# Cargador_RasPi3HAT_CamSlot_v1_1.net
KiCad netlist of a schematic drawn in EAGLE
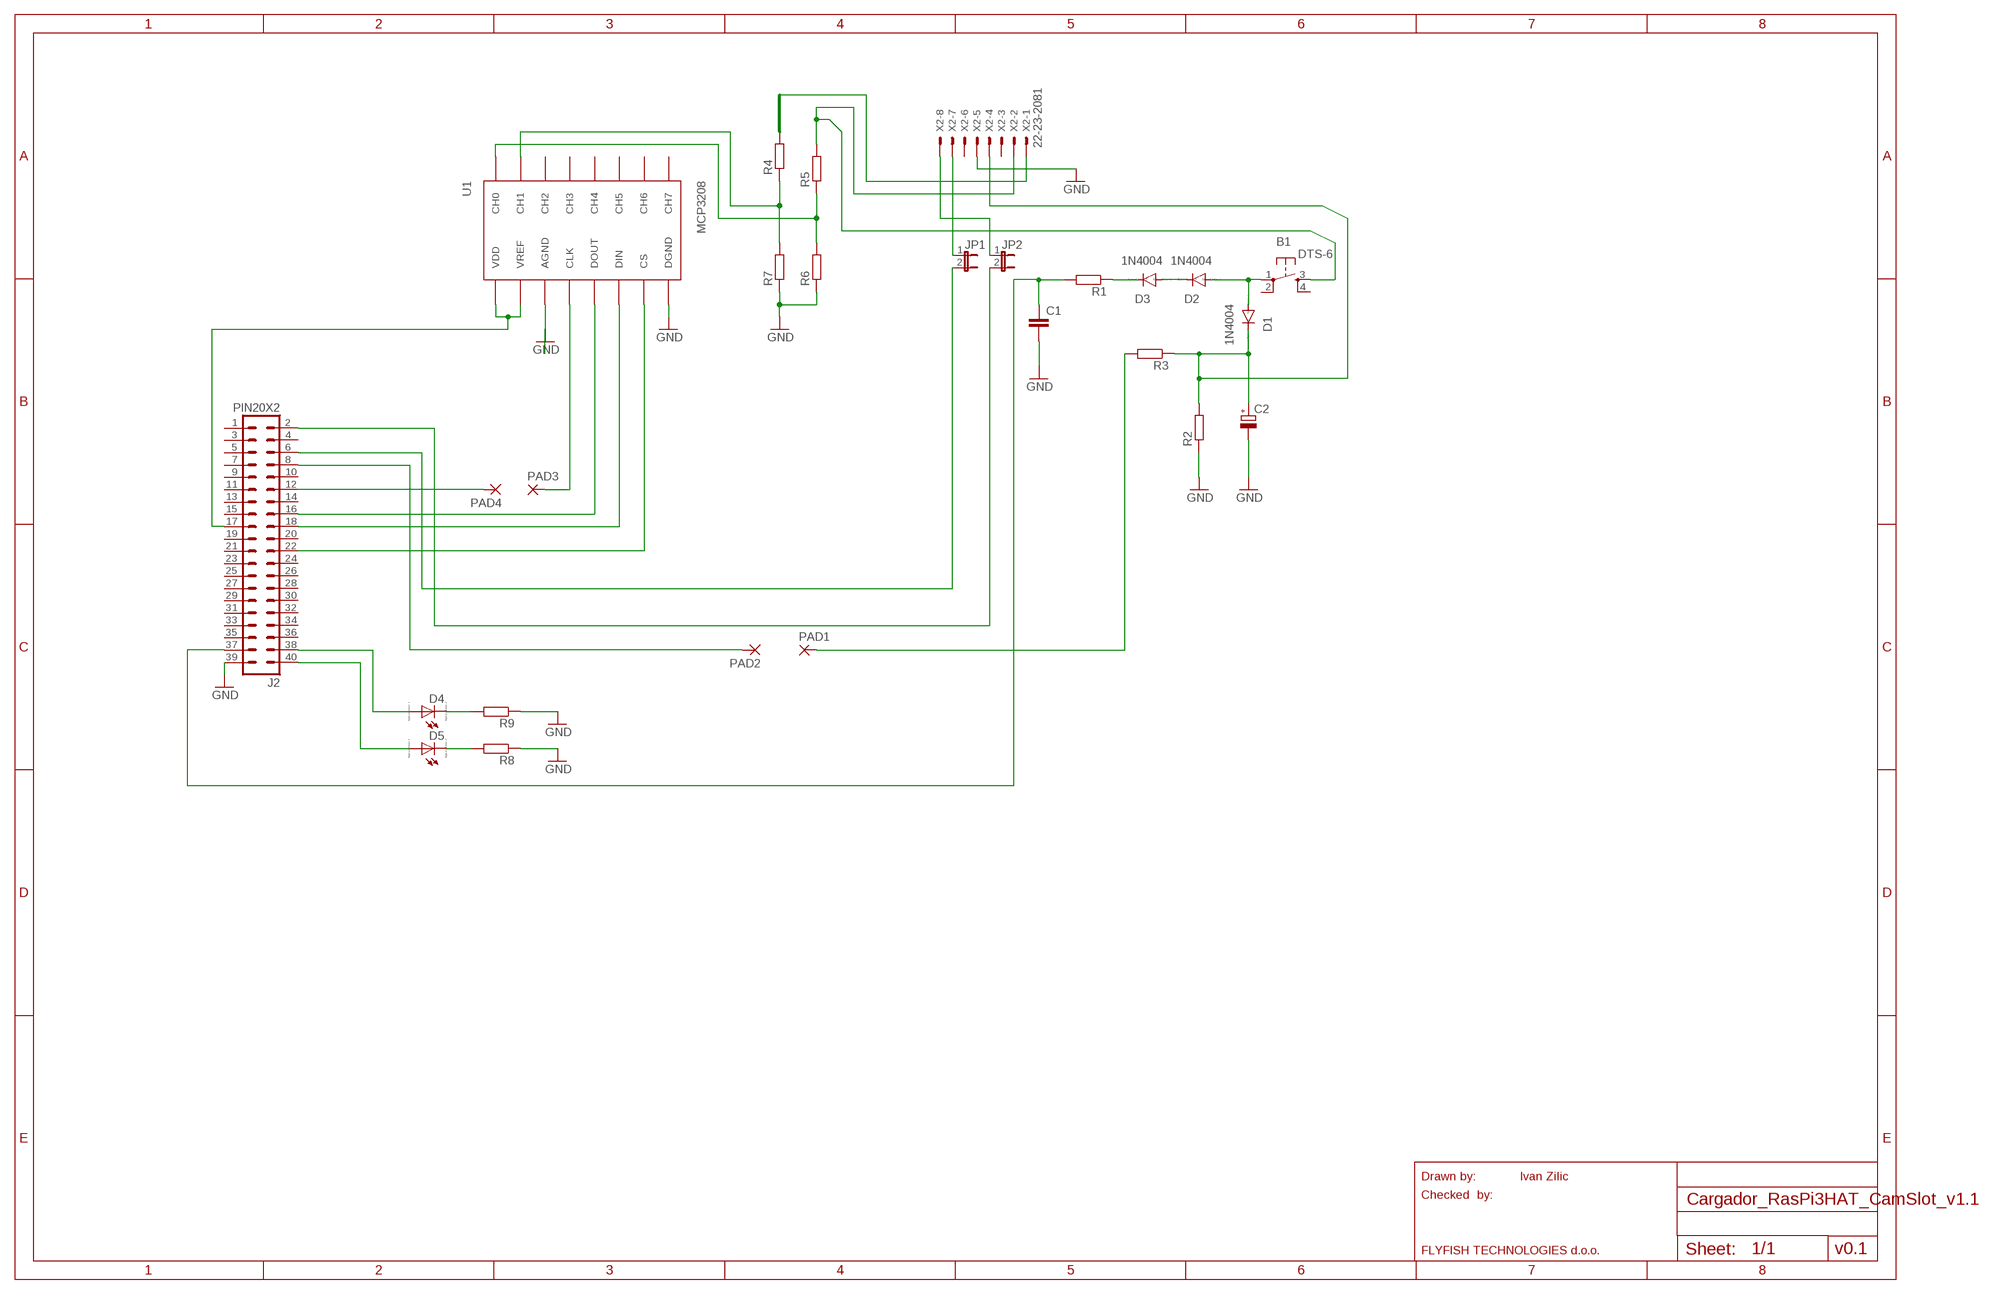
[diagram p0: schematic, sheet 1]

(export (version "E")
  (design (tool "Eeschema 10.0.6"))
  (components
    (comp (ref "B1")
      (value "DTS-6")
      (footprint "eagle-import:DTS-6")
      (libsource (lib "eagle-import") (part "DTS-6"))
    )
    (comp (ref "C1")
      (value "C2.5/2")
      (footprint "eagle-import:C2.5-2")
      (libsource (lib "eagle-import") (part "C2.5/2"))
    )
    (comp (ref "C2")
      (value "CPOL-EUE5-4")
      (footprint "eagle-import:E5-4")
      (libsource (lib "eagle-import") (part "CPOL-EUE5-4"))
    )
    (comp (ref "D1")
      (value "1N4004")
      (footprint "eagle-import:DO41-10")
      (libsource (lib "eagle-import") (part "1N4004"))
    )
    (comp (ref "D2")
      (value "1N4004")
      (footprint "eagle-import:DO41-10")
      (libsource (lib "eagle-import") (part "1N4004"))
    )
    (comp (ref "D3")
      (value "1N4004")
      (footprint "eagle-import:DO41-10")
      (libsource (lib "eagle-import") (part "1N4004"))
    )
    (comp (ref "D4")
      (value "LED_ELD260")
      (footprint "eagle-import:LED_LD260")
      (libsource (lib "eagle-import") (part "LED_ELD260"))
    )
    (comp (ref "D5")
      (value "LED_ELD260")
      (footprint "eagle-import:LED_LD260")
      (libsource (lib "eagle-import") (part "LED_ELD260"))
    )
    (comp (ref "J2")
      (value "PIN20X2")
      (footprint "eagle-import:PIN_20X2")
      (libsource (lib "eagle-import") (part "PIN20X2"))
    )
    (comp (ref "JP1")
      (value "JP1E")
      (footprint "eagle-import:JP1")
      (libsource (lib "eagle-import") (part "JP1E"))
    )
    (comp (ref "JP2")
      (value "JP1E")
      (footprint "eagle-import:JP1")
      (libsource (lib "eagle-import") (part "JP1E"))
    )
    (comp (ref "PAD1")
      (value "2,15/1,0")
      (footprint "eagle-import:2,15_1,0")
      (libsource (lib "eagle-import") (part "2,15/1,0"))
    )
    (comp (ref "PAD2")
      (value "2,15/1,0")
      (footprint "eagle-import:2,15_1,0")
      (libsource (lib "eagle-import") (part "2,15/1,0"))
    )
    (comp (ref "PAD3")
      (value "2,15/1,0")
      (footprint "eagle-import:2,15_1,0")
      (libsource (lib "eagle-import") (part "2,15/1,0"))
    )
    (comp (ref "PAD4")
      (value "2,15/1,0")
      (footprint "eagle-import:2,15_1,0")
      (libsource (lib "eagle-import") (part "2,15/1,0"))
    )
    (comp (ref "R1")
      (value "R-EU_0207/10")
      (footprint "eagle-import:0207_10")
      (libsource (lib "eagle-import") (part "R-EU_0207/10"))
    )
    (comp (ref "R2")
      (value "R-EU_0207/10")
      (footprint "eagle-import:0207_10")
      (libsource (lib "eagle-import") (part "R-EU_0207/10"))
    )
    (comp (ref "R3")
      (value "R-EU_0207/10")
      (footprint "eagle-import:0207_10")
      (libsource (lib "eagle-import") (part "R-EU_0207/10"))
    )
    (comp (ref "R4")
      (value "R-EU_0207/10")
      (footprint "eagle-import:0207_10")
      (libsource (lib "eagle-import") (part "R-EU_0207/10"))
    )
    (comp (ref "R5")
      (value "R-EU_0207/10")
      (footprint "eagle-import:0207_10")
      (libsource (lib "eagle-import") (part "R-EU_0207/10"))
    )
    (comp (ref "R6")
      (value "R-EU_0207/10")
      (footprint "eagle-import:0207_10")
      (libsource (lib "eagle-import") (part "R-EU_0207/10"))
    )
    (comp (ref "R7")
      (value "R-EU_0207/10")
      (footprint "eagle-import:0207_10")
      (libsource (lib "eagle-import") (part "R-EU_0207/10"))
    )
    (comp (ref "R8")
      (value "R-EU_0207/10")
      (footprint "eagle-import:0207_10")
      (libsource (lib "eagle-import") (part "R-EU_0207/10"))
    )
    (comp (ref "R9")
      (value "R-EU_0207/10")
      (footprint "eagle-import:0207_10")
      (libsource (lib "eagle-import") (part "R-EU_0207/10"))
    )
    (comp (ref "U1")
      (value "MCP3208")
      (footprint "eagle-import:DIL16")
      (libsource (lib "eagle-import") (part "MCP3208"))
    )
    (comp (ref "X2")
      (value "22-23-2081")
      (footprint "eagle-import:22-23-2081")
      (fields (field (name "MF") "MOLEX"))
      (libsource (lib "eagle-import") (part "22-23-2081"))
    )
  )
  (nets
    (net (code "1") (name "GND") (class "Default")
      (node (ref "C1") (pin "2") (pinfunction "2_2") (pintype "passive"))
      (node (ref "C2") (pin "-") (pinfunction "-_-") (pintype "passive"))
      (node (ref "J2") (pin "39") (pinfunction "39_39") (pintype "passive"))
      (node (ref "R2") (pin "1") (pinfunction "1_1") (pintype "passive"))
      (node (ref "R6") (pin "1") (pinfunction "1_1") (pintype "passive"))
      (node (ref "R7") (pin "1") (pinfunction "1_1") (pintype "passive"))
      (node (ref "R8") (pin "1") (pinfunction "1_1") (pintype "passive"))
      (node (ref "R9") (pin "1") (pinfunction "1_1") (pintype "passive"))
      (node (ref "U1") (pin "AGND") (pinfunction "AGND_AGND") (pintype "power_in"))
      (node (ref "U1") (pin "DGND") (pinfunction "DGND_DGND") (pintype "power_in"))
      (node (ref "X2") (pin "5") (pinfunction "S_5") (pintype "passive"))
    )
    (net (code "2") (name "Net-(B1-Pad1)") (class "Default")
      (node (ref "B1") (pin "1") (pinfunction "1_1") (pintype "passive"))
      (node (ref "D1") (pin "A") (pinfunction "A_A") (pintype "passive"))
      (node (ref "D2") (pin "A") (pinfunction "A_A") (pintype "passive"))
    )
    (net (code "3") (name "Net-(C1-Pad1)") (class "Default")
      (node (ref "C1") (pin "1") (pinfunction "1_1") (pintype "passive"))
      (node (ref "J2") (pin "37") (pinfunction "37_37") (pintype "passive"))
      (node (ref "R1") (pin "2") (pinfunction "2_2") (pintype "passive"))
    )
    (net (code "4") (name "Net-(D2-PadC)") (class "Default")
      (node (ref "D2") (pin "C") (pinfunction "C_C") (pintype "passive"))
      (node (ref "D3") (pin "A") (pinfunction "A_A") (pintype "passive"))
    )
    (net (code "5") (name "Net-(D3-PadC)") (class "Default")
      (node (ref "D3") (pin "C") (pinfunction "C_C") (pintype "passive"))
      (node (ref "R1") (pin "1") (pinfunction "1_1") (pintype "passive"))
    )
    (net (code "6") (name "Net-(D4-C)") (class "Default")
      (node (ref "D4") (pin "K") (pinfunction "C_K") (pintype "passive"))
      (node (ref "R9") (pin "2") (pinfunction "2_2") (pintype "passive"))
    )
    (net (code "7") (name "Net-(D4-PadA)") (class "Default")
      (node (ref "D4") (pin "A") (pinfunction "A_A") (pintype "passive"))
      (node (ref "J2") (pin "38") (pinfunction "38_38") (pintype "passive"))
    )
    (net (code "8") (name "Net-(D5-C)") (class "Default")
      (node (ref "D5") (pin "K") (pinfunction "C_K") (pintype "passive"))
      (node (ref "R8") (pin "2") (pinfunction "2_2") (pintype "passive"))
    )
    (net (code "9") (name "Net-(D5-PadA)") (class "Default")
      (node (ref "D5") (pin "A") (pinfunction "A_A") (pintype "passive"))
      (node (ref "J2") (pin "40") (pinfunction "40_40") (pintype "passive"))
    )
    (net (code "10") (name "Net-(J2-Pad2)") (class "Default")
      (node (ref "J2") (pin "2") (pinfunction "2_2") (pintype "passive"))
      (node (ref "JP2") (pin "2") (pinfunction "2_2") (pintype "passive"))
    )
    (net (code "11") (name "Net-(J2-Pad6)") (class "Default")
      (node (ref "J2") (pin "6") (pinfunction "6_6") (pintype "passive"))
      (node (ref "JP1") (pin "2") (pinfunction "2_2") (pintype "passive"))
    )
    (net (code "12") (name "Net-(J2-Pad16)") (class "Default")
      (node (ref "J2") (pin "16") (pinfunction "16_16") (pintype "passive"))
      (node (ref "U1") (pin "DOUT") (pinfunction "DOUT_DOUT") (pintype "output"))
    )
    (net (code "13") (name "Net-(J2-Pad17)") (class "Default")
      (node (ref "J2") (pin "17") (pinfunction "17_17") (pintype "passive"))
      (node (ref "U1") (pin "VDD") (pinfunction "VDD_VDD") (pintype "power_in"))
      (node (ref "U1") (pin "VREF") (pinfunction "VREF_VREF") (pintype "input"))
    )
    (net (code "14") (name "Net-(J2-Pad18)") (class "Default")
      (node (ref "J2") (pin "18") (pinfunction "18_18") (pintype "passive"))
      (node (ref "U1") (pin "DIN") (pinfunction "DIN_DIN") (pintype "input"))
    )
    (net (code "15") (name "Net-(J2-Pad22)") (class "Default")
      (node (ref "J2") (pin "22") (pinfunction "22_22") (pintype "passive"))
      (node (ref "U1") (pin "CS") (pinfunction "CS_CS") (pintype "input"))
    )
    (net (code "16") (name "Net-(PAD1-P)") (class "Default")
      (node (ref "PAD1") (pin "1") (pinfunction "P_1") (pintype "passive"))
      (node (ref "R3") (pin "2") (pinfunction "2_2") (pintype "passive"))
    )
    (net (code "17") (name "Net-(PAD2-P)") (class "Default")
      (node (ref "J2") (pin "8") (pinfunction "8_8") (pintype "passive"))
      (node (ref "PAD2") (pin "1") (pinfunction "P_1") (pintype "passive"))
    )
    (net (code "18") (name "Net-(PAD3-P)") (class "Default")
      (node (ref "PAD3") (pin "1") (pinfunction "P_1") (pintype "passive"))
      (node (ref "U1") (pin "CLK") (pinfunction "CLK_CLK") (pintype "input"))
    )
    (net (code "19") (name "Net-(PAD4-P)") (class "Default")
      (node (ref "J2") (pin "12") (pinfunction "12_12") (pintype "passive"))
      (node (ref "PAD4") (pin "1") (pinfunction "P_1") (pintype "passive"))
    )
    (net (code "20") (name "Net-(R4-Pad1)") (class "Default")
      (node (ref "R4") (pin "1") (pinfunction "1_1") (pintype "passive"))
      (node (ref "R7") (pin "2") (pinfunction "2_2") (pintype "passive"))
      (node (ref "U1") (pin "CH1") (pinfunction "CH1_CH1") (pintype "input"))
    )
    (net (code "21") (name "Net-(R5-Pad1)") (class "Default")
      (node (ref "R5") (pin "1") (pinfunction "1_1") (pintype "passive"))
      (node (ref "R6") (pin "2") (pinfunction "2_2") (pintype "passive"))
      (node (ref "U1") (pin "CH0") (pinfunction "CH0_CH0") (pintype "input"))
    )
    (net (code "22") (name "Net-(X2A-S)") (class "Default")
      (node (ref "R4") (pin "2") (pinfunction "2_2") (pintype "passive"))
      (node (ref "X2") (pin "1") (pinfunction "S_1") (pintype "passive"))
    )
    (net (code "23") (name "Net-(X2B-S)") (class "Default")
      (node (ref "B1") (pin "3") (pinfunction "3_3") (pintype "passive"))
      (node (ref "R5") (pin "2") (pinfunction "2_2") (pintype "passive"))
      (node (ref "X2") (pin "2") (pinfunction "S_2") (pintype "passive"))
    )
    (net (code "24") (name "Net-(X2D-S)") (class "Default")
      (node (ref "C2") (pin "+") (pinfunction "+_+") (pintype "passive"))
      (node (ref "D1") (pin "C") (pinfunction "C_C") (pintype "passive"))
      (node (ref "R2") (pin "2") (pinfunction "2_2") (pintype "passive"))
      (node (ref "R3") (pin "1") (pinfunction "1_1") (pintype "passive"))
      (node (ref "X2") (pin "4") (pinfunction "S_4") (pintype "passive"))
    )
    (net (code "25") (name "Net-(X2G-S)") (class "Default")
      (node (ref "JP1") (pin "1") (pinfunction "1_1") (pintype "passive"))
      (node (ref "X2") (pin "7") (pinfunction "S_7") (pintype "passive"))
    )
    (net (code "26") (name "Net-(X2H-S)") (class "Default")
      (node (ref "JP2") (pin "1") (pinfunction "1_1") (pintype "passive"))
      (node (ref "X2") (pin "8") (pinfunction "S_8") (pintype "passive"))
    )
    (net (code "27") (name "unconnected-(B1-Pad2)") (class "Default")
      (node (ref "B1") (pin "2") (pinfunction "2_2") (pintype "passive"))
    )
    (net (code "28") (name "unconnected-(B1-Pad4)") (class "Default")
      (node (ref "B1") (pin "4") (pinfunction "4_4") (pintype "passive"))
    )
    (net (code "29") (name "unconnected-(J2-Pad1)") (class "Default")
      (node (ref "J2") (pin "1") (pinfunction "1_1") (pintype "passive"))
    )
    (net (code "30") (name "unconnected-(J2-Pad3)") (class "Default")
      (node (ref "J2") (pin "3") (pinfunction "3_3") (pintype "passive"))
    )
    (net (code "31") (name "unconnected-(J2-Pad4)") (class "Default")
      (node (ref "J2") (pin "4") (pinfunction "4_4") (pintype "passive"))
    )
    (net (code "32") (name "unconnected-(J2-Pad5)") (class "Default")
      (node (ref "J2") (pin "5") (pinfunction "5_5") (pintype "passive"))
    )
    (net (code "33") (name "unconnected-(J2-Pad7)") (class "Default")
      (node (ref "J2") (pin "7") (pinfunction "7_7") (pintype "passive"))
    )
    (net (code "34") (name "unconnected-(J2-Pad9)") (class "Default")
      (node (ref "J2") (pin "9") (pinfunction "9_9") (pintype "passive"))
    )
    (net (code "35") (name "unconnected-(J2-Pad10)") (class "Default")
      (node (ref "J2") (pin "10") (pinfunction "10_10") (pintype "passive"))
    )
    (net (code "36") (name "unconnected-(J2-Pad11)") (class "Default")
      (node (ref "J2") (pin "11") (pinfunction "11_11") (pintype "passive"))
    )
    (net (code "37") (name "unconnected-(J2-Pad13)") (class "Default")
      (node (ref "J2") (pin "13") (pinfunction "13_13") (pintype "passive"))
    )
    (net (code "38") (name "unconnected-(J2-Pad14)") (class "Default")
      (node (ref "J2") (pin "14") (pinfunction "14_14") (pintype "passive"))
    )
    (net (code "39") (name "unconnected-(J2-Pad15)") (class "Default")
      (node (ref "J2") (pin "15") (pinfunction "15_15") (pintype "passive"))
    )
    (net (code "40") (name "unconnected-(J2-Pad19)") (class "Default")
      (node (ref "J2") (pin "19") (pinfunction "19_19") (pintype "passive"))
    )
    (net (code "41") (name "unconnected-(J2-Pad20)") (class "Default")
      (node (ref "J2") (pin "20") (pinfunction "20_20") (pintype "passive"))
    )
    (net (code "42") (name "unconnected-(J2-Pad21)") (class "Default")
      (node (ref "J2") (pin "21") (pinfunction "21_21") (pintype "passive"))
    )
    (net (code "43") (name "unconnected-(J2-Pad23)") (class "Default")
      (node (ref "J2") (pin "23") (pinfunction "23_23") (pintype "passive"))
    )
    (net (code "44") (name "unconnected-(J2-Pad24)") (class "Default")
      (node (ref "J2") (pin "24") (pinfunction "24_24") (pintype "passive"))
    )
    (net (code "45") (name "unconnected-(J2-Pad25)") (class "Default")
      (node (ref "J2") (pin "25") (pinfunction "25_25") (pintype "passive"))
    )
    (net (code "46") (name "unconnected-(J2-Pad26)") (class "Default")
      (node (ref "J2") (pin "26") (pinfunction "26_26") (pintype "passive"))
    )
    (net (code "47") (name "unconnected-(J2-Pad27)") (class "Default")
      (node (ref "J2") (pin "27") (pinfunction "27_27") (pintype "passive"))
    )
    (net (code "48") (name "unconnected-(J2-Pad28)") (class "Default")
      (node (ref "J2") (pin "28") (pinfunction "28_28") (pintype "passive"))
    )
    (net (code "49") (name "unconnected-(J2-Pad29)") (class "Default")
      (node (ref "J2") (pin "29") (pinfunction "29_29") (pintype "passive"))
    )
    (net (code "50") (name "unconnected-(J2-Pad30)") (class "Default")
      (node (ref "J2") (pin "30") (pinfunction "30_30") (pintype "passive"))
    )
    (net (code "51") (name "unconnected-(J2-Pad31)") (class "Default")
      (node (ref "J2") (pin "31") (pinfunction "31_31") (pintype "passive"))
    )
    (net (code "52") (name "unconnected-(J2-Pad32)") (class "Default")
      (node (ref "J2") (pin "32") (pinfunction "32_32") (pintype "passive"))
    )
    (net (code "53") (name "unconnected-(J2-Pad33)") (class "Default")
      (node (ref "J2") (pin "33") (pinfunction "33_33") (pintype "passive"))
    )
    (net (code "54") (name "unconnected-(J2-Pad34)") (class "Default")
      (node (ref "J2") (pin "34") (pinfunction "34_34") (pintype "passive"))
    )
    (net (code "55") (name "unconnected-(J2-Pad35)") (class "Default")
      (node (ref "J2") (pin "35") (pinfunction "35_35") (pintype "passive"))
    )
    (net (code "56") (name "unconnected-(J2-Pad36)") (class "Default")
      (node (ref "J2") (pin "36") (pinfunction "36_36") (pintype "passive"))
    )
    (net (code "57") (name "unconnected-(U1-PadCH2)") (class "Default")
      (node (ref "U1") (pin "CH2") (pinfunction "CH2_CH2") (pintype "input"))
    )
    (net (code "58") (name "unconnected-(U1-PadCH3)") (class "Default")
      (node (ref "U1") (pin "CH3") (pinfunction "CH3_CH3") (pintype "input"))
    )
    (net (code "59") (name "unconnected-(U1-PadCH4)") (class "Default")
      (node (ref "U1") (pin "CH4") (pinfunction "CH4_CH4") (pintype "input"))
    )
    (net (code "60") (name "unconnected-(U1-PadCH5)") (class "Default")
      (node (ref "U1") (pin "CH5") (pinfunction "CH5_CH5") (pintype "input"))
    )
    (net (code "61") (name "unconnected-(U1-PadCH6)") (class "Default")
      (node (ref "U1") (pin "CH6") (pinfunction "CH6_CH6") (pintype "input"))
    )
    (net (code "62") (name "unconnected-(U1-PadCH7)") (class "Default")
      (node (ref "U1") (pin "CH7") (pinfunction "CH7_CH7") (pintype "input"))
    )
    (net (code "63") (name "unconnected-(X2C-S-Pad3)") (class "Default")
      (node (ref "X2") (pin "3") (pinfunction "S_3") (pintype "passive"))
    )
    (net (code "64") (name "unconnected-(X2F-S-Pad6)") (class "Default")
      (node (ref "X2") (pin "6") (pinfunction "S_6") (pintype "passive"))
    )
  )
)
